# SCH_weatherstation_2024-12-12.net
KiCad netlist of a schematic drawn in EasyEDA
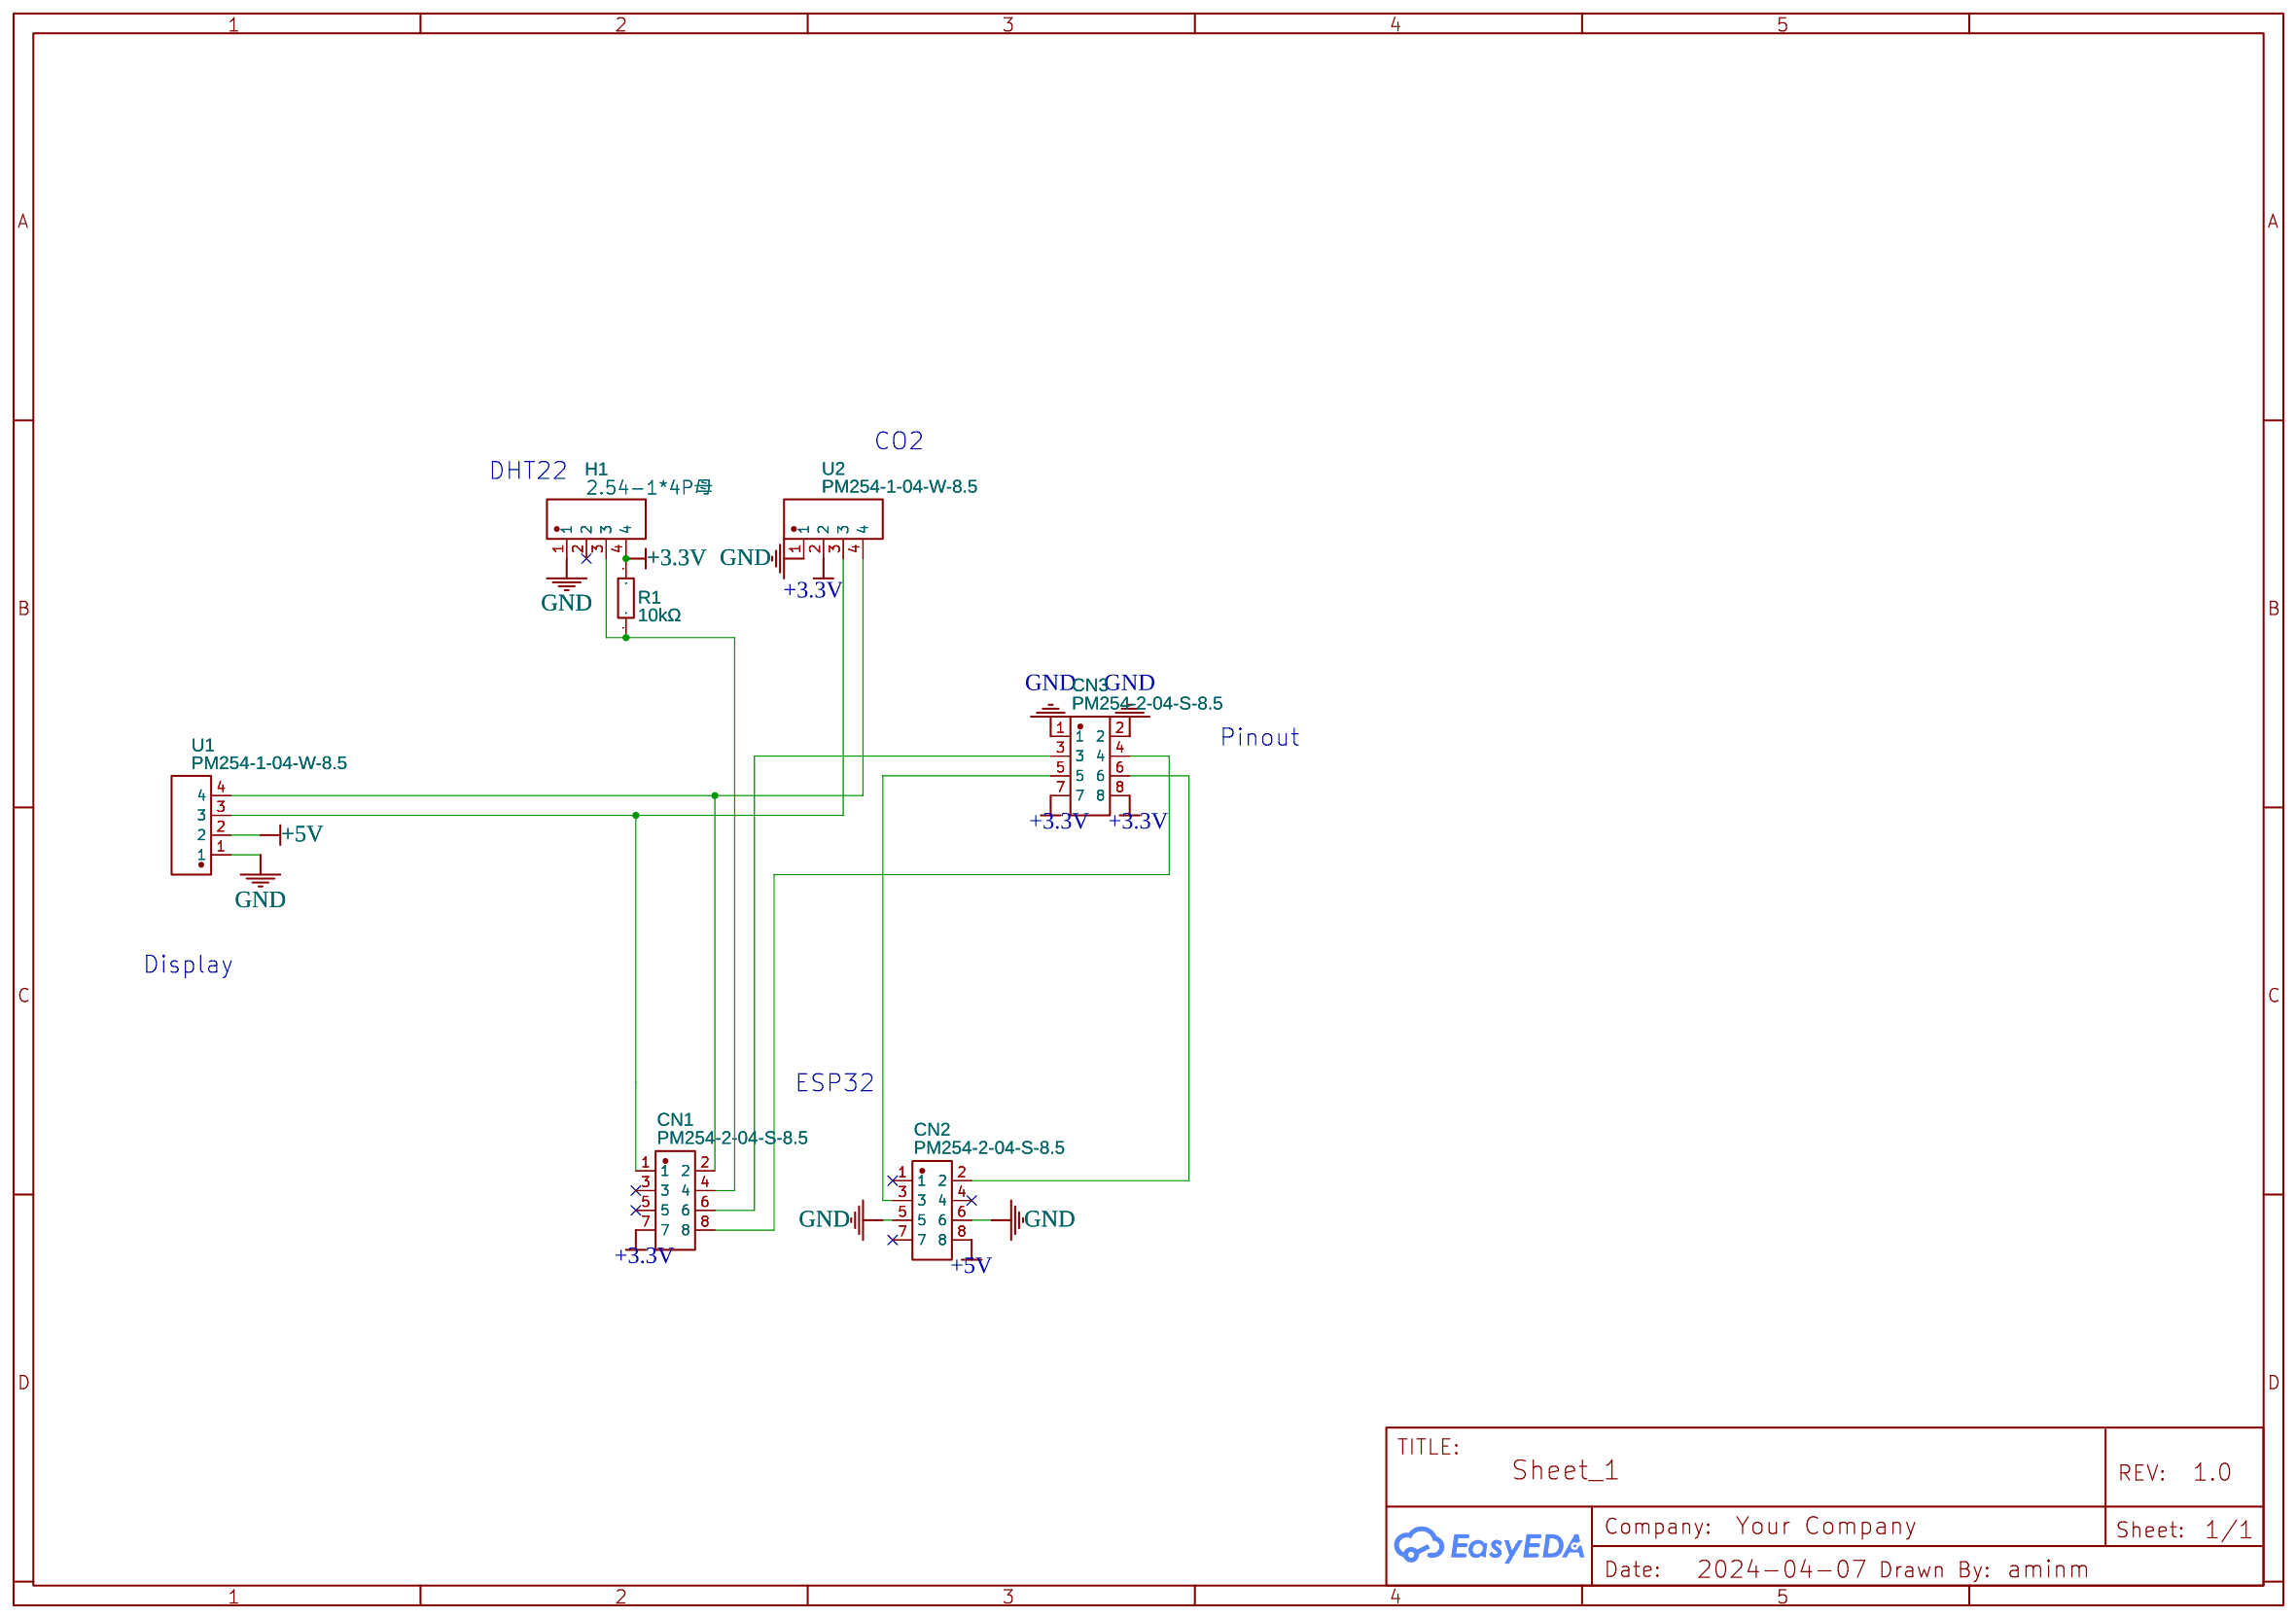
[diagram p0: schematic sheet]

(export (version "E")
  (design (tool "Eeschema 10.0.6"))
  (components
    (comp (ref "CN1")
      (value "PM254-2-04-S-8.5")
      (fields (field (name "Manufacturer") "HCTL(华灿天禄)"))
      (libsource (lib "") (part "PM254-2-04-S-8.5"))
    )
    (comp (ref "CN2")
      (value "PM254-2-04-S-8.5")
      (fields (field (name "Manufacturer") "HCTL(华灿天禄)"))
      (libsource (lib "") (part "PM254-2-04-S-8.5"))
    )
    (comp (ref "CN3")
      (value "PM254-2-04-S-8.5")
      (fields (field (name "Manufacturer") "HCTL(华灿天禄)"))
      (libsource (lib "") (part "PM254-2-04-S-8.5"))
    )
    (comp (ref "H1")
      (value "2.54-1*4P母")
      (fields (field (name "Manufacturer") "BOOMELE(博穆精密)"))
      (libsource (lib "") (part "2.54-1*4P母"))
    )
    (comp (ref "R1")
      (value "10kΩ")
      (fields
        (field (name "Manufacturer Part") "0603WAF1002T5E")
        (field (name "Manufacturer") "UNI-ROYAL(厚声)")
      )
      (libsource (lib "") (part "0603WAF1002T5E"))
    )
    (comp (ref "U1")
      (value "PM254-1-04-W-8.5")
      (fields (field (name "Manufacturer") "HCTL(华灿天禄)"))
      (libsource (lib "") (part "PM254-1-04-W-8.5"))
    )
    (comp (ref "U2")
      (value "PM254-1-04-W-8.5")
      (fields (field (name "Manufacturer") "HCTL(华灿天禄)"))
      (libsource (lib "") (part "PM254-1-04-W-8.5_1"))
    )
  )
  (nets
    (net (code "1") (name "+3.3V") (class "Default")
      (node (ref "CN1") (pin "7") (pinfunction "7_7") (pintype "unspecified"))
      (node (ref "CN3") (pin "7") (pinfunction "7_7") (pintype "unspecified"))
      (node (ref "CN3") (pin "8") (pinfunction "8_8") (pintype "unspecified"))
      (node (ref "H1") (pin "4") (pinfunction "4_4") (pintype "unspecified"))
      (node (ref "R1") (pin "2") (pinfunction "2_2") (pintype "input"))
      (node (ref "U2") (pin "2") (pinfunction "2_2") (pintype "unspecified"))
    )
    (net (code "2") (name "+5V") (class "Default")
      (node (ref "CN2") (pin "8") (pinfunction "8_8") (pintype "unspecified"))
      (node (ref "U1") (pin "2") (pinfunction "2_2") (pintype "unspecified"))
    )
    (net (code "3") (name "GND") (class "Default")
      (node (ref "CN2") (pin "5") (pinfunction "5_5") (pintype "unspecified"))
      (node (ref "CN2") (pin "6") (pinfunction "6_6") (pintype "unspecified"))
      (node (ref "CN3") (pin "1") (pinfunction "1_1") (pintype "unspecified"))
      (node (ref "CN3") (pin "2") (pinfunction "2_2") (pintype "unspecified"))
      (node (ref "H1") (pin "1") (pinfunction "1_1") (pintype "unspecified"))
      (node (ref "U1") (pin "1") (pinfunction "1_1") (pintype "unspecified"))
      (node (ref "U2") (pin "1") (pinfunction "1_1") (pintype "unspecified"))
    )
    (net (code "4") (name "Net-(CN1-Pad1)") (class "Default")
      (node (ref "CN1") (pin "1") (pinfunction "1_1") (pintype "unspecified"))
      (node (ref "U1") (pin "3") (pinfunction "3_3") (pintype "unspecified"))
      (node (ref "U2") (pin "3") (pinfunction "3_3") (pintype "unspecified"))
    )
    (net (code "5") (name "Net-(CN1-Pad2)") (class "Default")
      (node (ref "CN1") (pin "2") (pinfunction "2_2") (pintype "unspecified"))
      (node (ref "U1") (pin "4") (pinfunction "4_4") (pintype "unspecified"))
      (node (ref "U2") (pin "4") (pinfunction "4_4") (pintype "unspecified"))
    )
    (net (code "6") (name "Net-(CN1-Pad4)") (class "Default")
      (node (ref "CN1") (pin "4") (pinfunction "4_4") (pintype "unspecified"))
      (node (ref "H1") (pin "3") (pinfunction "3_3") (pintype "unspecified"))
      (node (ref "R1") (pin "1") (pinfunction "1_1") (pintype "input"))
    )
    (net (code "7") (name "Net-(CN1-Pad6)") (class "Default")
      (node (ref "CN1") (pin "6") (pinfunction "6_6") (pintype "unspecified"))
      (node (ref "CN3") (pin "3") (pinfunction "3_3") (pintype "unspecified"))
    )
    (net (code "8") (name "Net-(CN1-Pad8)") (class "Default")
      (node (ref "CN1") (pin "8") (pinfunction "8_8") (pintype "unspecified"))
      (node (ref "CN3") (pin "4") (pinfunction "4_4") (pintype "unspecified"))
    )
    (net (code "9") (name "Net-(CN2-Pad2)") (class "Default")
      (node (ref "CN2") (pin "2") (pinfunction "2_2") (pintype "unspecified"))
      (node (ref "CN3") (pin "6") (pinfunction "6_6") (pintype "unspecified"))
    )
    (net (code "10") (name "Net-(CN2-Pad3)") (class "Default")
      (node (ref "CN2") (pin "3") (pinfunction "3_3") (pintype "unspecified"))
      (node (ref "CN3") (pin "5") (pinfunction "5_5") (pintype "unspecified"))
    )
    (net (code "11") (name "unconnected-(CN1-Pad3)") (class "Default")
      (node (ref "CN1") (pin "3") (pinfunction "3_3") (pintype "unspecified+no_connect"))
    )
    (net (code "12") (name "unconnected-(CN1-Pad5)") (class "Default")
      (node (ref "CN1") (pin "5") (pinfunction "5_5") (pintype "unspecified+no_connect"))
    )
    (net (code "13") (name "unconnected-(CN2-Pad1)") (class "Default")
      (node (ref "CN2") (pin "1") (pinfunction "1_1") (pintype "unspecified+no_connect"))
    )
    (net (code "14") (name "unconnected-(CN2-Pad4)") (class "Default")
      (node (ref "CN2") (pin "4") (pinfunction "4_4") (pintype "unspecified+no_connect"))
    )
    (net (code "15") (name "unconnected-(CN2-Pad7)") (class "Default")
      (node (ref "CN2") (pin "7") (pinfunction "7_7") (pintype "unspecified+no_connect"))
    )
    (net (code "16") (name "unconnected-(H1-Pad2)") (class "Default")
      (node (ref "H1") (pin "2") (pinfunction "2_2") (pintype "unspecified+no_connect"))
    )
  )
)
